# KIK01_LED_Brd.net
KiCad netlist of a schematic drawn in EAGLE
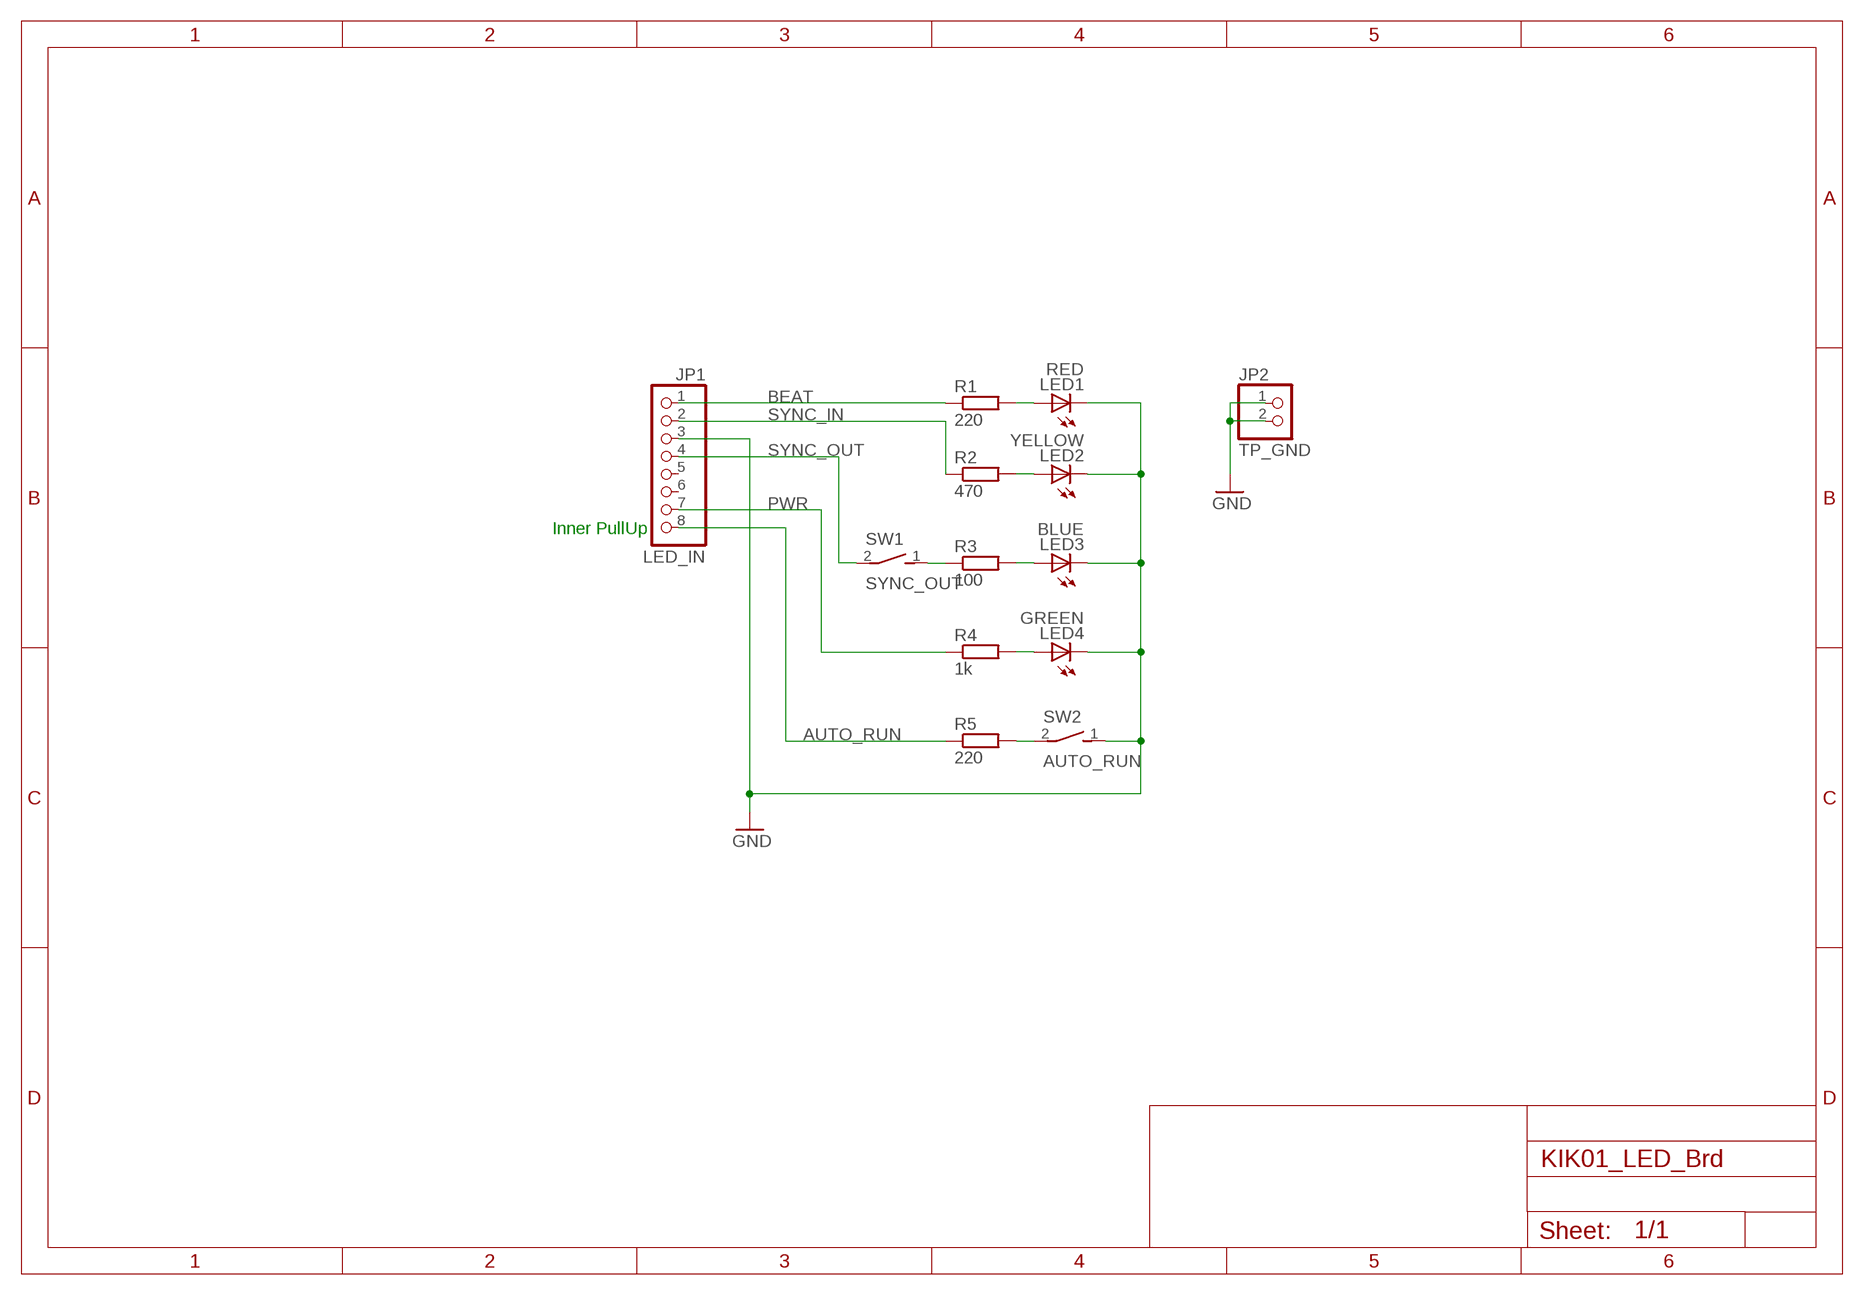
[diagram p0: schematic, sheet 1]

(export (version "E")
  (design (tool "Eeschema 10.0.6"))
  (components
    (comp (ref "JP1")
      (value "LED_IN")
      (footprint "eagle-import:1X08")
      (libsource (lib "eagle-import") (part "PINHD-1X8"))
    )
    (comp (ref "JP2")
      (value "TP_GND")
      (footprint "eagle-import:1X02")
      (libsource (lib "eagle-import") (part "PINHD-1X2"))
    )
    (comp (ref "LED1")
      (value "RED")
      (footprint "eagle-import:LED3MM")
      (libsource (lib "eagle-import") (part "LED3MM"))
    )
    (comp (ref "LED2")
      (value "YELLOW")
      (footprint "eagle-import:LED3MM")
      (libsource (lib "eagle-import") (part "LED3MM"))
    )
    (comp (ref "LED3")
      (value "BLUE")
      (footprint "eagle-import:LED3MM")
      (libsource (lib "eagle-import") (part "LED3MM"))
    )
    (comp (ref "LED4")
      (value "GREEN")
      (footprint "eagle-import:LED3MM")
      (libsource (lib "eagle-import") (part "LED3MM"))
    )
    (comp (ref "R1")
      (value "220")
      (footprint "eagle-import:0204_7")
      (libsource (lib "eagle-import") (part "R-EU_0204/7"))
    )
    (comp (ref "R2")
      (value "470")
      (footprint "eagle-import:0204_7")
      (libsource (lib "eagle-import") (part "R-EU_0204/7"))
    )
    (comp (ref "R3")
      (value "100")
      (footprint "eagle-import:0204_7")
      (libsource (lib "eagle-import") (part "R-EU_0204/7"))
    )
    (comp (ref "R4")
      (value "1k")
      (footprint "eagle-import:0204_7")
      (libsource (lib "eagle-import") (part "R-EU_0204/7"))
    )
    (comp (ref "R5")
      (value "220")
      (footprint "eagle-import:0204_7")
      (libsource (lib "eagle-import") (part "R-EU_0204/7"))
    )
    (comp (ref "SW1")
      (value "SYNC_OUT")
      (footprint "eagle-import:TOGGLE_SW_SPST")
      (libsource (lib "eagle-import") (part "TOGGLE_SW_SPST"))
    )
    (comp (ref "SW2")
      (value "AUTO_RUN")
      (footprint "eagle-import:TOGGLE_SW_SPST")
      (libsource (lib "eagle-import") (part "TOGGLE_SW_SPST"))
    )
  )
  (nets
    (net (code "1") (name "/AUTO_RUN") (class "Default")
      (node (ref "JP1") (pin "8") (pinfunction "8_8") (pintype "passive"))
      (node (ref "R5") (pin "1") (pinfunction "1_1") (pintype "passive"))
    )
    (net (code "2") (name "/BEAT") (class "Default")
      (node (ref "JP1") (pin "1") (pinfunction "1_1") (pintype "passive"))
      (node (ref "R1") (pin "1") (pinfunction "1_1") (pintype "passive"))
    )
    (net (code "3") (name "/PWR") (class "Default")
      (node (ref "JP1") (pin "7") (pinfunction "7_7") (pintype "passive"))
      (node (ref "R4") (pin "1") (pinfunction "1_1") (pintype "passive"))
    )
    (net (code "4") (name "/SYNC_IN") (class "Default")
      (node (ref "JP1") (pin "2") (pinfunction "2_2") (pintype "passive"))
      (node (ref "R2") (pin "1") (pinfunction "1_1") (pintype "passive"))
    )
    (net (code "5") (name "/SYNC_OUT") (class "Default")
      (node (ref "JP1") (pin "4") (pinfunction "4_4") (pintype "passive"))
      (node (ref "SW1") (pin "2") (pinfunction "P_2") (pintype "passive"))
    )
    (net (code "6") (name "GND") (class "Default")
      (node (ref "JP1") (pin "3") (pinfunction "3_3") (pintype "passive"))
      (node (ref "JP2") (pin "1") (pinfunction "1_1") (pintype "passive"))
      (node (ref "JP2") (pin "2") (pinfunction "2_2") (pintype "passive"))
      (node (ref "LED1") (pin "K") (pinfunction "C_K") (pintype "passive"))
      (node (ref "LED2") (pin "K") (pinfunction "C_K") (pintype "passive"))
      (node (ref "LED3") (pin "K") (pinfunction "C_K") (pintype "passive"))
      (node (ref "LED4") (pin "K") (pinfunction "C_K") (pintype "passive"))
      (node (ref "SW2") (pin "1") (pinfunction "S_1") (pintype "passive"))
    )
    (net (code "7") (name "Net-(LED1-PadA)") (class "Default")
      (node (ref "LED1") (pin "A") (pinfunction "A_A") (pintype "passive"))
      (node (ref "R1") (pin "2") (pinfunction "2_2") (pintype "passive"))
    )
    (net (code "8") (name "Net-(LED2-PadA)") (class "Default")
      (node (ref "LED2") (pin "A") (pinfunction "A_A") (pintype "passive"))
      (node (ref "R2") (pin "2") (pinfunction "2_2") (pintype "passive"))
    )
    (net (code "9") (name "Net-(LED3-PadA)") (class "Default")
      (node (ref "LED3") (pin "A") (pinfunction "A_A") (pintype "passive"))
      (node (ref "R3") (pin "2") (pinfunction "2_2") (pintype "passive"))
    )
    (net (code "10") (name "Net-(LED4-PadA)") (class "Default")
      (node (ref "LED4") (pin "A") (pinfunction "A_A") (pintype "passive"))
      (node (ref "R4") (pin "2") (pinfunction "2_2") (pintype "passive"))
    )
    (net (code "11") (name "Net-(SW1-S)") (class "Default")
      (node (ref "R3") (pin "1") (pinfunction "1_1") (pintype "passive"))
      (node (ref "SW1") (pin "1") (pinfunction "S_1") (pintype "passive"))
    )
    (net (code "12") (name "Net-(SW2-P)") (class "Default")
      (node (ref "R5") (pin "2") (pinfunction "2_2") (pintype "passive"))
      (node (ref "SW2") (pin "2") (pinfunction "P_2") (pintype "passive"))
    )
    (net (code "13") (name "unconnected-(JP1-Pad5)") (class "Default")
      (node (ref "JP1") (pin "5") (pinfunction "5_5") (pintype "passive"))
    )
    (net (code "14") (name "unconnected-(JP1-Pad6)") (class "Default")
      (node (ref "JP1") (pin "6") (pinfunction "6_6") (pintype "passive"))
    )
  )
)
